# EvalBoard_MUXandTouchController_v0_2a.net
KiCad netlist of a schematic drawn in EAGLE
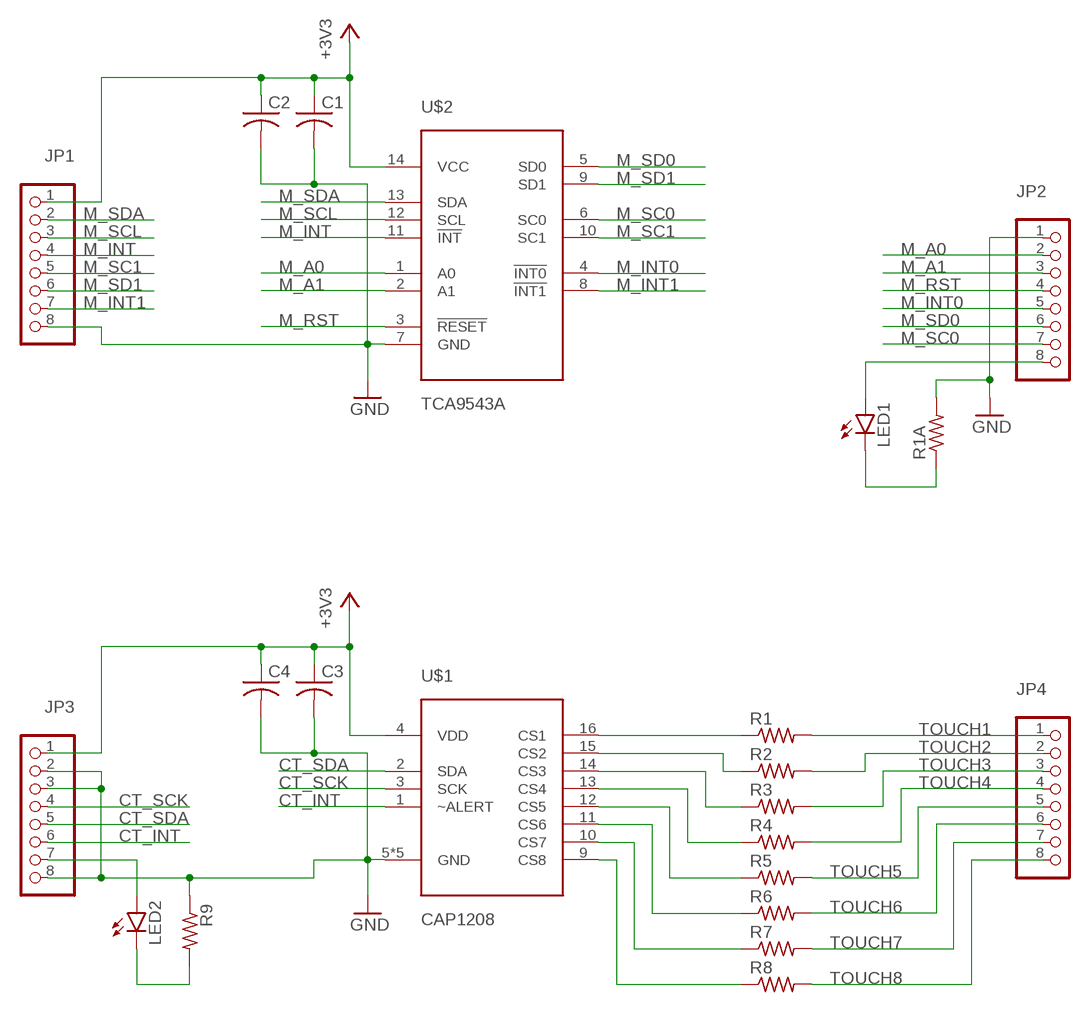
[diagram p0: schematic, sheet 1]

(export (version "E")
  (design (tool "Eeschema 10.0.6"))
  (components
    (comp (ref "C1")
      (value "C-USC0603")
      (footprint "eagle-import:C0603")
      (libsource (lib "eagle-import") (part "C-USC0603"))
    )
    (comp (ref "C2")
      (value "C-USC0603")
      (footprint "eagle-import:C0603")
      (libsource (lib "eagle-import") (part "C-USC0603"))
    )
    (comp (ref "C3")
      (value "C-USC0603")
      (footprint "eagle-import:C0603")
      (libsource (lib "eagle-import") (part "C-USC0603"))
    )
    (comp (ref "C4")
      (value "C-USC0603")
      (footprint "eagle-import:C0603")
      (libsource (lib "eagle-import") (part "C-USC0603"))
    )
    (comp (ref "JP1")
      (value "PINHD-1X8BIG")
      (footprint "eagle-import:1X08-BIG")
      (libsource (lib "eagle-import") (part "PINHD-1X8BIG"))
    )
    (comp (ref "JP2")
      (value "PINHD-1X8BIG")
      (footprint "eagle-import:1X08-BIG")
      (libsource (lib "eagle-import") (part "PINHD-1X8BIG"))
    )
    (comp (ref "JP3")
      (value "PINHD-1X8BIG")
      (footprint "eagle-import:1X08-BIG")
      (libsource (lib "eagle-import") (part "PINHD-1X8BIG"))
    )
    (comp (ref "JP4")
      (value "PINHD-1X8BIG")
      (footprint "eagle-import:1X08-BIG")
      (libsource (lib "eagle-import") (part "PINHD-1X8BIG"))
    )
    (comp (ref "LED1")
      (value "LEDCHIP-LED0603")
      (footprint "eagle-import:CHIP-LED0603")
      (libsource (lib "eagle-import") (part "LEDCHIP-LED0603"))
    )
    (comp (ref "LED2")
      (value "LEDCHIP-LED0603")
      (footprint "eagle-import:CHIP-LED0603")
      (libsource (lib "eagle-import") (part "LEDCHIP-LED0603"))
    )
    (comp (ref "R1")
      (value "R-US_R0603")
      (footprint "eagle-import:R0603")
      (libsource (lib "eagle-import") (part "R-US_R0603"))
    )
    (comp (ref "R1A")
      (value "R-US_R0603")
      (footprint "eagle-import:R0603")
      (libsource (lib "eagle-import") (part "R-US_R0603"))
    )
    (comp (ref "R2")
      (value "R-US_R0603")
      (footprint "eagle-import:R0603")
      (libsource (lib "eagle-import") (part "R-US_R0603"))
    )
    (comp (ref "R3")
      (value "R-US_R0603")
      (footprint "eagle-import:R0603")
      (libsource (lib "eagle-import") (part "R-US_R0603"))
    )
    (comp (ref "R4")
      (value "R-US_R0603")
      (footprint "eagle-import:R0603")
      (libsource (lib "eagle-import") (part "R-US_R0603"))
    )
    (comp (ref "R5")
      (value "R-US_R0603")
      (footprint "eagle-import:R0603")
      (libsource (lib "eagle-import") (part "R-US_R0603"))
    )
    (comp (ref "R6")
      (value "R-US_R0603")
      (footprint "eagle-import:R0603")
      (libsource (lib "eagle-import") (part "R-US_R0603"))
    )
    (comp (ref "R7")
      (value "R-US_R0603")
      (footprint "eagle-import:R0603")
      (libsource (lib "eagle-import") (part "R-US_R0603"))
    )
    (comp (ref "R8")
      (value "R-US_R0603")
      (footprint "eagle-import:R0603")
      (libsource (lib "eagle-import") (part "R-US_R0603"))
    )
    (comp (ref "R9")
      (value "R-US_R0603")
      (footprint "eagle-import:R0603")
      (libsource (lib "eagle-import") (part "R-US_R0603"))
    )
    (comp (ref "U$1")
      (value "CAP1208")
      (footprint "eagle-import:QFN-16-3X3")
      (libsource (lib "eagle-import") (part "CAP1208"))
    )
    (comp (ref "U$2")
      (value "TCA9543A")
      (footprint "eagle-import:TSSOP-14")
      (libsource (lib "eagle-import") (part "TCA9543A"))
    )
  )
  (nets
    (net (code "1") (name "+3V3") (class "Default")
      (node (ref "C1") (pin "1") (pinfunction "1_1") (pintype "passive"))
      (node (ref "C2") (pin "1") (pinfunction "1_1") (pintype "passive"))
      (node (ref "C3") (pin "1") (pinfunction "1_1") (pintype "passive"))
      (node (ref "C4") (pin "1") (pinfunction "1_1") (pintype "passive"))
      (node (ref "JP1") (pin "1") (pinfunction "1_1") (pintype "passive"))
      (node (ref "JP3") (pin "1") (pinfunction "1_1") (pintype "passive"))
      (node (ref "U$1") (pin "4") (pinfunction "VDD_4") (pintype "power_in"))
      (node (ref "U$2") (pin "14") (pinfunction "VCC_14") (pintype "power_in"))
    )
    (net (code "2") (name "/CT_INT") (class "Default")
      (node (ref "JP3") (pin "6") (pinfunction "6_6") (pintype "passive"))
      (node (ref "U$1") (pin "1") (pinfunction "~{ALERT}_1") (pintype "output"))
    )
    (net (code "3") (name "/CT_SCK") (class "Default")
      (node (ref "JP3") (pin "4") (pinfunction "4_4") (pintype "passive"))
      (node (ref "U$1") (pin "3") (pinfunction "SCK_3") (pintype "bidirectional"))
    )
    (net (code "4") (name "/CT_SDA") (class "Default")
      (node (ref "JP3") (pin "5") (pinfunction "5_5") (pintype "passive"))
      (node (ref "U$1") (pin "2") (pinfunction "SDA_2") (pintype "bidirectional"))
    )
    (net (code "5") (name "/M_A0") (class "Default")
      (node (ref "JP2") (pin "2") (pinfunction "2_2") (pintype "passive"))
      (node (ref "U$2") (pin "1") (pinfunction "A0_1") (pintype "input"))
    )
    (net (code "6") (name "/M_A1") (class "Default")
      (node (ref "JP2") (pin "3") (pinfunction "3_3") (pintype "passive"))
      (node (ref "U$2") (pin "2") (pinfunction "A1_2") (pintype "input"))
    )
    (net (code "7") (name "/M_INT") (class "Default")
      (node (ref "JP1") (pin "4") (pinfunction "4_4") (pintype "passive"))
      (node (ref "U$2") (pin "11") (pinfunction "~{INT}_11") (pintype "output"))
    )
    (net (code "8") (name "/M_INT0") (class "Default")
      (node (ref "JP2") (pin "5") (pinfunction "5_5") (pintype "passive"))
      (node (ref "U$2") (pin "4") (pinfunction "~{INT0}_4") (pintype "bidirectional"))
    )
    (net (code "9") (name "/M_INT1") (class "Default")
      (node (ref "JP1") (pin "7") (pinfunction "7_7") (pintype "passive"))
      (node (ref "U$2") (pin "8") (pinfunction "~{INT1}_8") (pintype "bidirectional"))
    )
    (net (code "10") (name "/M_RST") (class "Default")
      (node (ref "JP2") (pin "4") (pinfunction "4_4") (pintype "passive"))
      (node (ref "U$2") (pin "3") (pinfunction "~{RESET}_3") (pintype "input"))
    )
    (net (code "11") (name "/M_SC0") (class "Default")
      (node (ref "JP2") (pin "7") (pinfunction "7_7") (pintype "passive"))
      (node (ref "U$2") (pin "6") (pinfunction "SC0_6") (pintype "bidirectional"))
    )
    (net (code "12") (name "/M_SC1") (class "Default")
      (node (ref "JP1") (pin "5") (pinfunction "5_5") (pintype "passive"))
      (node (ref "U$2") (pin "10") (pinfunction "SC1_10") (pintype "bidirectional"))
    )
    (net (code "13") (name "/M_SCL") (class "Default")
      (node (ref "JP1") (pin "3") (pinfunction "3_3") (pintype "passive"))
      (node (ref "U$2") (pin "12") (pinfunction "SCL_12") (pintype "bidirectional"))
    )
    (net (code "14") (name "/M_SD0") (class "Default")
      (node (ref "JP2") (pin "6") (pinfunction "6_6") (pintype "passive"))
      (node (ref "U$2") (pin "5") (pinfunction "SD0_5") (pintype "bidirectional"))
    )
    (net (code "15") (name "/M_SD1") (class "Default")
      (node (ref "JP1") (pin "6") (pinfunction "6_6") (pintype "passive"))
      (node (ref "U$2") (pin "9") (pinfunction "SD1_9") (pintype "bidirectional"))
    )
    (net (code "16") (name "/M_SDA") (class "Default")
      (node (ref "JP1") (pin "2") (pinfunction "2_2") (pintype "passive"))
      (node (ref "U$2") (pin "13") (pinfunction "SDA_13") (pintype "bidirectional"))
    )
    (net (code "17") (name "/TOUCH1") (class "Default")
      (node (ref "JP4") (pin "1") (pinfunction "1_1") (pintype "passive"))
      (node (ref "R1") (pin "2") (pinfunction "2_2") (pintype "passive"))
    )
    (net (code "18") (name "/TOUCH2") (class "Default")
      (node (ref "JP4") (pin "2") (pinfunction "2_2") (pintype "passive"))
      (node (ref "R2") (pin "2") (pinfunction "2_2") (pintype "passive"))
    )
    (net (code "19") (name "/TOUCH3") (class "Default")
      (node (ref "JP4") (pin "3") (pinfunction "3_3") (pintype "passive"))
      (node (ref "R3") (pin "2") (pinfunction "2_2") (pintype "passive"))
    )
    (net (code "20") (name "/TOUCH4") (class "Default")
      (node (ref "JP4") (pin "4") (pinfunction "4_4") (pintype "passive"))
      (node (ref "R4") (pin "2") (pinfunction "2_2") (pintype "passive"))
    )
    (net (code "21") (name "/TOUCH5") (class "Default")
      (node (ref "JP4") (pin "5") (pinfunction "5_5") (pintype "passive"))
      (node (ref "R5") (pin "2") (pinfunction "2_2") (pintype "passive"))
    )
    (net (code "22") (name "/TOUCH6") (class "Default")
      (node (ref "JP4") (pin "6") (pinfunction "6_6") (pintype "passive"))
      (node (ref "R6") (pin "2") (pinfunction "2_2") (pintype "passive"))
    )
    (net (code "23") (name "/TOUCH7") (class "Default")
      (node (ref "JP4") (pin "7") (pinfunction "7_7") (pintype "passive"))
      (node (ref "R7") (pin "2") (pinfunction "2_2") (pintype "passive"))
    )
    (net (code "24") (name "/TOUCH8") (class "Default")
      (node (ref "JP4") (pin "8") (pinfunction "8_8") (pintype "passive"))
      (node (ref "R8") (pin "2") (pinfunction "2_2") (pintype "passive"))
    )
    (net (code "25") (name "GND") (class "Default")
      (node (ref "C1") (pin "2") (pinfunction "2_2") (pintype "passive"))
      (node (ref "C2") (pin "2") (pinfunction "2_2") (pintype "passive"))
      (node (ref "C3") (pin "2") (pinfunction "2_2") (pintype "passive"))
      (node (ref "C4") (pin "2") (pinfunction "2_2") (pintype "passive"))
      (node (ref "JP1") (pin "8") (pinfunction "8_8") (pintype "passive"))
      (node (ref "JP2") (pin "1") (pinfunction "1_1") (pintype "passive"))
      (node (ref "JP3") (pin "2") (pinfunction "2_2") (pintype "passive"))
      (node (ref "JP3") (pin "3") (pinfunction "3_3") (pintype "passive"))
      (node (ref "JP3") (pin "8") (pinfunction "8_8") (pintype "passive"))
      (node (ref "R1A") (pin "2") (pinfunction "2_2") (pintype "passive"))
      (node (ref "R9") (pin "1") (pinfunction "1_1") (pintype "passive"))
      (node (ref "U$1") (pin "5") (pinfunction "GND_5") (pintype "power_in"))
      (node (ref "U$1") (pin "6") (pinfunction "GND_6") (pintype "power_in"))
      (node (ref "U$1") (pin "7") (pinfunction "GND_7") (pintype "power_in"))
      (node (ref "U$1") (pin "8") (pinfunction "GND_8") (pintype "power_in"))
      (node (ref "U$1") (pin "PAD") (pinfunction "GND_PAD") (pintype "power_in"))
      (node (ref "U$2") (pin "7") (pinfunction "GND_7") (pintype "power_in"))
    )
    (net (code "26") (name "Net-(JP2-Pad8)") (class "Default")
      (node (ref "JP2") (pin "8") (pinfunction "8_8") (pintype "passive"))
      (node (ref "LED1") (pin "A") (pinfunction "A_A") (pintype "passive"))
    )
    (net (code "27") (name "Net-(JP3-Pad7)") (class "Default")
      (node (ref "JP3") (pin "7") (pinfunction "7_7") (pintype "passive"))
      (node (ref "LED2") (pin "A") (pinfunction "A_A") (pintype "passive"))
    )
    (net (code "28") (name "Net-(LED1-PadC)") (class "Default")
      (node (ref "LED1") (pin "C") (pinfunction "C_C") (pintype "passive"))
      (node (ref "R1A") (pin "1") (pinfunction "1_1") (pintype "passive"))
    )
    (net (code "29") (name "Net-(LED2-PadC)") (class "Default")
      (node (ref "LED2") (pin "C") (pinfunction "C_C") (pintype "passive"))
      (node (ref "R9") (pin "2") (pinfunction "2_2") (pintype "passive"))
    )
    (net (code "30") (name "Net-(U$1-CS1)") (class "Default")
      (node (ref "R1") (pin "1") (pinfunction "1_1") (pintype "passive"))
      (node (ref "U$1") (pin "16") (pinfunction "CS1_16") (pintype "input"))
    )
    (net (code "31") (name "Net-(U$1-CS2)") (class "Default")
      (node (ref "R2") (pin "1") (pinfunction "1_1") (pintype "passive"))
      (node (ref "U$1") (pin "15") (pinfunction "CS2_15") (pintype "input"))
    )
    (net (code "32") (name "Net-(U$1-CS3)") (class "Default")
      (node (ref "R3") (pin "1") (pinfunction "1_1") (pintype "passive"))
      (node (ref "U$1") (pin "14") (pinfunction "CS3_14") (pintype "input"))
    )
    (net (code "33") (name "Net-(U$1-CS4)") (class "Default")
      (node (ref "R4") (pin "1") (pinfunction "1_1") (pintype "passive"))
      (node (ref "U$1") (pin "13") (pinfunction "CS4_13") (pintype "input"))
    )
    (net (code "34") (name "Net-(U$1-CS5)") (class "Default")
      (node (ref "R5") (pin "1") (pinfunction "1_1") (pintype "passive"))
      (node (ref "U$1") (pin "12") (pinfunction "CS5_12") (pintype "input"))
    )
    (net (code "35") (name "Net-(U$1-CS6)") (class "Default")
      (node (ref "R6") (pin "1") (pinfunction "1_1") (pintype "passive"))
      (node (ref "U$1") (pin "11") (pinfunction "CS6_11") (pintype "input"))
    )
    (net (code "36") (name "Net-(U$1-CS7)") (class "Default")
      (node (ref "R7") (pin "1") (pinfunction "1_1") (pintype "passive"))
      (node (ref "U$1") (pin "10") (pinfunction "CS7_10") (pintype "input"))
    )
    (net (code "37") (name "Net-(U$1-CS8)") (class "Default")
      (node (ref "R8") (pin "1") (pinfunction "1_1") (pintype "passive"))
      (node (ref "U$1") (pin "9") (pinfunction "CS8_9") (pintype "input"))
    )
  )
)
